# AutoCAD_Cloudv2_1.net
KiCad netlist of a schematic drawn in EAGLE
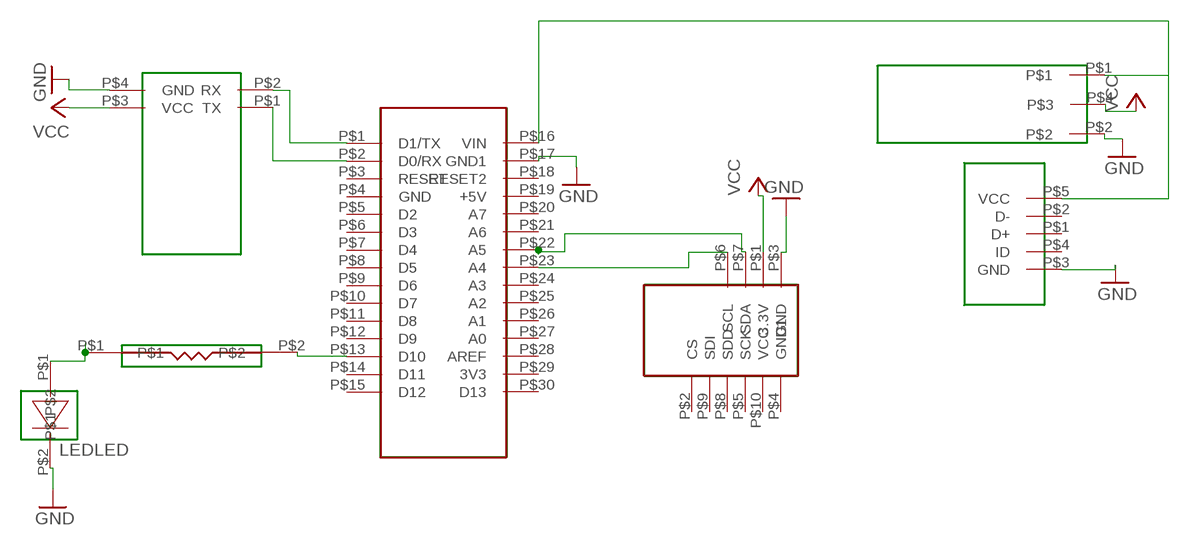
[diagram p0: schematic, sheet 1]

(export (version "E")
  (design (tool "Eeschema 10.0.6"))
  (components
    (comp (ref "U$1")
      (value "1KOHM1KOHM")
      (footprint "eagle-import:1KOHM")
      (libsource (lib "eagle-import") (part "1KOHM1KOHM"))
    )
    (comp (ref "U$2")
      (value "ARDUINONANOARDUINONAONO")
      (footprint "eagle-import:ARDUINONANO")
      (libsource (lib "eagle-import") (part "ARDUINONANOARDUINONAONO"))
    )
    (comp (ref "U$3")
      (value "BM240BM240")
      (footprint "eagle-import:BM240")
      (libsource (lib "eagle-import") (part "BM240BM240"))
    )
    (comp (ref "U$4")
      (value "LEDLED")
      (footprint "eagle-import:LED")
      (libsource (lib "eagle-import") (part "LEDLED"))
    )
    (comp (ref "U$5")
      (value "LMC3V3LMC3V3")
      (footprint "eagle-import:LMC3V3")
      (libsource (lib "eagle-import") (part "LMC3V3LMC3V3"))
    )
    (comp (ref "U$6")
      (value "RN41RN41")
      (footprint "eagle-import:RN41")
      (libsource (lib "eagle-import") (part "RN41RN41"))
    )
    (comp (ref "U$7")
      (value "USBUSB")
      (footprint "eagle-import:USB")
      (libsource (lib "eagle-import") (part "USBUSB"))
    )
  )
  (nets
    (net (code "1") (name "GND") (class "Default")
      (node (ref "U$2") (pin "P$17") (pinfunction "GND1_P$17") (pintype "bidirectional"))
      (node (ref "U$3") (pin "P$3") (pinfunction "GND_P$3") (pintype "bidirectional"))
      (node (ref "U$4") (pin "P$2") (pinfunction "P$2_P$2") (pintype "bidirectional"))
      (node (ref "U$5") (pin "P$2") (pinfunction "P$2_P$2") (pintype "bidirectional"))
      (node (ref "U$6") (pin "P$4") (pinfunction "GND_P$4") (pintype "bidirectional"))
      (node (ref "U$7") (pin "P$3") (pinfunction "GND_P$3") (pintype "bidirectional"))
    )
    (net (code "2") (name "Net-(U$1-PadP$1)") (class "Default")
      (node (ref "U$1") (pin "P$1") (pinfunction "P$1_P$1") (pintype "bidirectional"))
      (node (ref "U$4") (pin "P$1") (pinfunction "P$1_P$1") (pintype "bidirectional"))
    )
    (net (code "3") (name "Net-(U$2-A4)") (class "Default")
      (node (ref "U$2") (pin "P$23") (pinfunction "A4_P$23") (pintype "bidirectional"))
      (node (ref "U$3") (pin "P$6") (pinfunction "SCL_P$6") (pintype "bidirectional"))
    )
    (net (code "4") (name "Net-(U$2-A5)") (class "Default")
      (node (ref "U$2") (pin "P$22") (pinfunction "A5_P$22") (pintype "bidirectional"))
      (node (ref "U$3") (pin "P$7") (pinfunction "SDA_P$7") (pintype "bidirectional"))
    )
    (net (code "5") (name "Net-(U$2-D0{slash}RX)") (class "Default")
      (node (ref "U$2") (pin "P$2") (pinfunction "D0/RX_P$2") (pintype "bidirectional"))
      (node (ref "U$6") (pin "P$1") (pinfunction "TX_P$1") (pintype "bidirectional"))
    )
    (net (code "6") (name "Net-(U$2-D1{slash}TX)") (class "Default")
      (node (ref "U$2") (pin "P$1") (pinfunction "D1/TX_P$1") (pintype "bidirectional"))
      (node (ref "U$6") (pin "P$2") (pinfunction "RX_P$2") (pintype "bidirectional"))
    )
    (net (code "7") (name "Net-(U$2-D10)") (class "Default")
      (node (ref "U$1") (pin "P$2") (pinfunction "P$2_P$2") (pintype "bidirectional"))
      (node (ref "U$2") (pin "P$13") (pinfunction "D10_P$13") (pintype "bidirectional"))
    )
    (net (code "8") (name "Net-(U$2-VIN)") (class "Default")
      (node (ref "U$2") (pin "P$16") (pinfunction "VIN_P$16") (pintype "bidirectional"))
      (node (ref "U$5") (pin "P$1") (pinfunction "P$1_P$1") (pintype "bidirectional"))
      (node (ref "U$7") (pin "P$5") (pinfunction "VCC_P$5") (pintype "bidirectional"))
    )
    (net (code "9") (name "VCC") (class "Default")
      (node (ref "U$3") (pin "P$1") (pinfunction "3.3V_P$1") (pintype "bidirectional"))
      (node (ref "U$5") (pin "P$4") (pinfunction "P$3_P$4") (pintype "bidirectional"))
      (node (ref "U$6") (pin "P$3") (pinfunction "VCC_P$3") (pintype "bidirectional"))
    )
    (net (code "10") (name "unconnected-(U$2-+5V-PadP$19)") (class "Default")
      (node (ref "U$2") (pin "P$19") (pinfunction "+5V_P$19") (pintype "bidirectional"))
    )
    (net (code "11") (name "unconnected-(U$2-3V3-PadP$29)") (class "Default")
      (node (ref "U$2") (pin "P$29") (pinfunction "3V3_P$29") (pintype "bidirectional"))
    )
    (net (code "12") (name "unconnected-(U$2-A0-PadP$27)") (class "Default")
      (node (ref "U$2") (pin "P$27") (pinfunction "A0_P$27") (pintype "bidirectional"))
    )
    (net (code "13") (name "unconnected-(U$2-A1-PadP$26)") (class "Default")
      (node (ref "U$2") (pin "P$26") (pinfunction "A1_P$26") (pintype "bidirectional"))
    )
    (net (code "14") (name "unconnected-(U$2-A2-PadP$25)") (class "Default")
      (node (ref "U$2") (pin "P$25") (pinfunction "A2_P$25") (pintype "bidirectional"))
    )
    (net (code "15") (name "unconnected-(U$2-A3-PadP$24)") (class "Default")
      (node (ref "U$2") (pin "P$24") (pinfunction "A3_P$24") (pintype "bidirectional"))
    )
    (net (code "16") (name "unconnected-(U$2-A6-PadP$21)") (class "Default")
      (node (ref "U$2") (pin "P$21") (pinfunction "A6_P$21") (pintype "bidirectional"))
    )
    (net (code "17") (name "unconnected-(U$2-A7-PadP$20)") (class "Default")
      (node (ref "U$2") (pin "P$20") (pinfunction "A7_P$20") (pintype "bidirectional"))
    )
    (net (code "18") (name "unconnected-(U$2-AREF-PadP$28)") (class "Default")
      (node (ref "U$2") (pin "P$28") (pinfunction "AREF_P$28") (pintype "bidirectional"))
    )
    (net (code "19") (name "unconnected-(U$2-D2-PadP$5)") (class "Default")
      (node (ref "U$2") (pin "P$5") (pinfunction "D2_P$5") (pintype "bidirectional"))
    )
    (net (code "20") (name "unconnected-(U$2-D3-PadP$6)") (class "Default")
      (node (ref "U$2") (pin "P$6") (pinfunction "D3_P$6") (pintype "bidirectional"))
    )
    (net (code "21") (name "unconnected-(U$2-D4-PadP$7)") (class "Default")
      (node (ref "U$2") (pin "P$7") (pinfunction "D4_P$7") (pintype "bidirectional"))
    )
    (net (code "22") (name "unconnected-(U$2-D5-PadP$8)") (class "Default")
      (node (ref "U$2") (pin "P$8") (pinfunction "D5_P$8") (pintype "bidirectional"))
    )
    (net (code "23") (name "unconnected-(U$2-D6-PadP$9)") (class "Default")
      (node (ref "U$2") (pin "P$9") (pinfunction "D6_P$9") (pintype "bidirectional"))
    )
    (net (code "24") (name "unconnected-(U$2-D7-PadP$10)") (class "Default")
      (node (ref "U$2") (pin "P$10") (pinfunction "D7_P$10") (pintype "bidirectional"))
    )
    (net (code "25") (name "unconnected-(U$2-D8-PadP$11)") (class "Default")
      (node (ref "U$2") (pin "P$11") (pinfunction "D8_P$11") (pintype "bidirectional"))
    )
    (net (code "26") (name "unconnected-(U$2-D9-PadP$12)") (class "Default")
      (node (ref "U$2") (pin "P$12") (pinfunction "D9_P$12") (pintype "bidirectional"))
    )
    (net (code "27") (name "unconnected-(U$2-D11-PadP$14)") (class "Default")
      (node (ref "U$2") (pin "P$14") (pinfunction "D11_P$14") (pintype "bidirectional"))
    )
    (net (code "28") (name "unconnected-(U$2-D12-PadP$15)") (class "Default")
      (node (ref "U$2") (pin "P$15") (pinfunction "D12_P$15") (pintype "bidirectional"))
    )
    (net (code "29") (name "unconnected-(U$2-D13-PadP$30)") (class "Default")
      (node (ref "U$2") (pin "P$30") (pinfunction "D13_P$30") (pintype "bidirectional"))
    )
    (net (code "30") (name "unconnected-(U$2-GND-PadP$4)") (class "Default")
      (node (ref "U$2") (pin "P$4") (pinfunction "GND_P$4") (pintype "bidirectional"))
    )
    (net (code "31") (name "unconnected-(U$2-RESET-PadP$3)") (class "Default")
      (node (ref "U$2") (pin "P$3") (pinfunction "RESET_P$3") (pintype "bidirectional"))
    )
    (net (code "32") (name "unconnected-(U$2-RESET2-PadP$18)") (class "Default")
      (node (ref "U$2") (pin "P$18") (pinfunction "RESET2_P$18") (pintype "bidirectional"))
    )
    (net (code "33") (name "unconnected-(U$3-CS-PadP$2)") (class "Default")
      (node (ref "U$3") (pin "P$2") (pinfunction "CS_P$2") (pintype "bidirectional"))
    )
    (net (code "34") (name "unconnected-(U$3-GND1-PadP$4)") (class "Default")
      (node (ref "U$3") (pin "P$4") (pinfunction "GND1_P$4") (pintype "bidirectional"))
    )
    (net (code "35") (name "unconnected-(U$3-SCK-PadP$5)") (class "Default")
      (node (ref "U$3") (pin "P$5") (pinfunction "SCK_P$5") (pintype "bidirectional"))
    )
    (net (code "36") (name "unconnected-(U$3-SDD-PadP$8)") (class "Default")
      (node (ref "U$3") (pin "P$8") (pinfunction "SDD_P$8") (pintype "bidirectional"))
    )
    (net (code "37") (name "unconnected-(U$3-SDI-PadP$9)") (class "Default")
      (node (ref "U$3") (pin "P$9") (pinfunction "SDI_P$9") (pintype "bidirectional"))
    )
    (net (code "38") (name "unconnected-(U$3-VCC-PadP$10)") (class "Default")
      (node (ref "U$3") (pin "P$10") (pinfunction "VCC_P$10") (pintype "bidirectional"))
    )
    (net (code "39") (name "unconnected-(U$7-D+-PadP$1)") (class "Default")
      (node (ref "U$7") (pin "P$1") (pinfunction "D+_P$1") (pintype "bidirectional"))
    )
    (net (code "40") (name "unconnected-(U$7-D--PadP$2)") (class "Default")
      (node (ref "U$7") (pin "P$2") (pinfunction "D-_P$2") (pintype "bidirectional"))
    )
    (net (code "41") (name "unconnected-(U$7-ID-PadP$4)") (class "Default")
      (node (ref "U$7") (pin "P$4") (pinfunction "ID_P$4") (pintype "bidirectional"))
    )
  )
)
